# rpi_display_v2.net
KiCad netlist of a schematic drawn in EAGLE
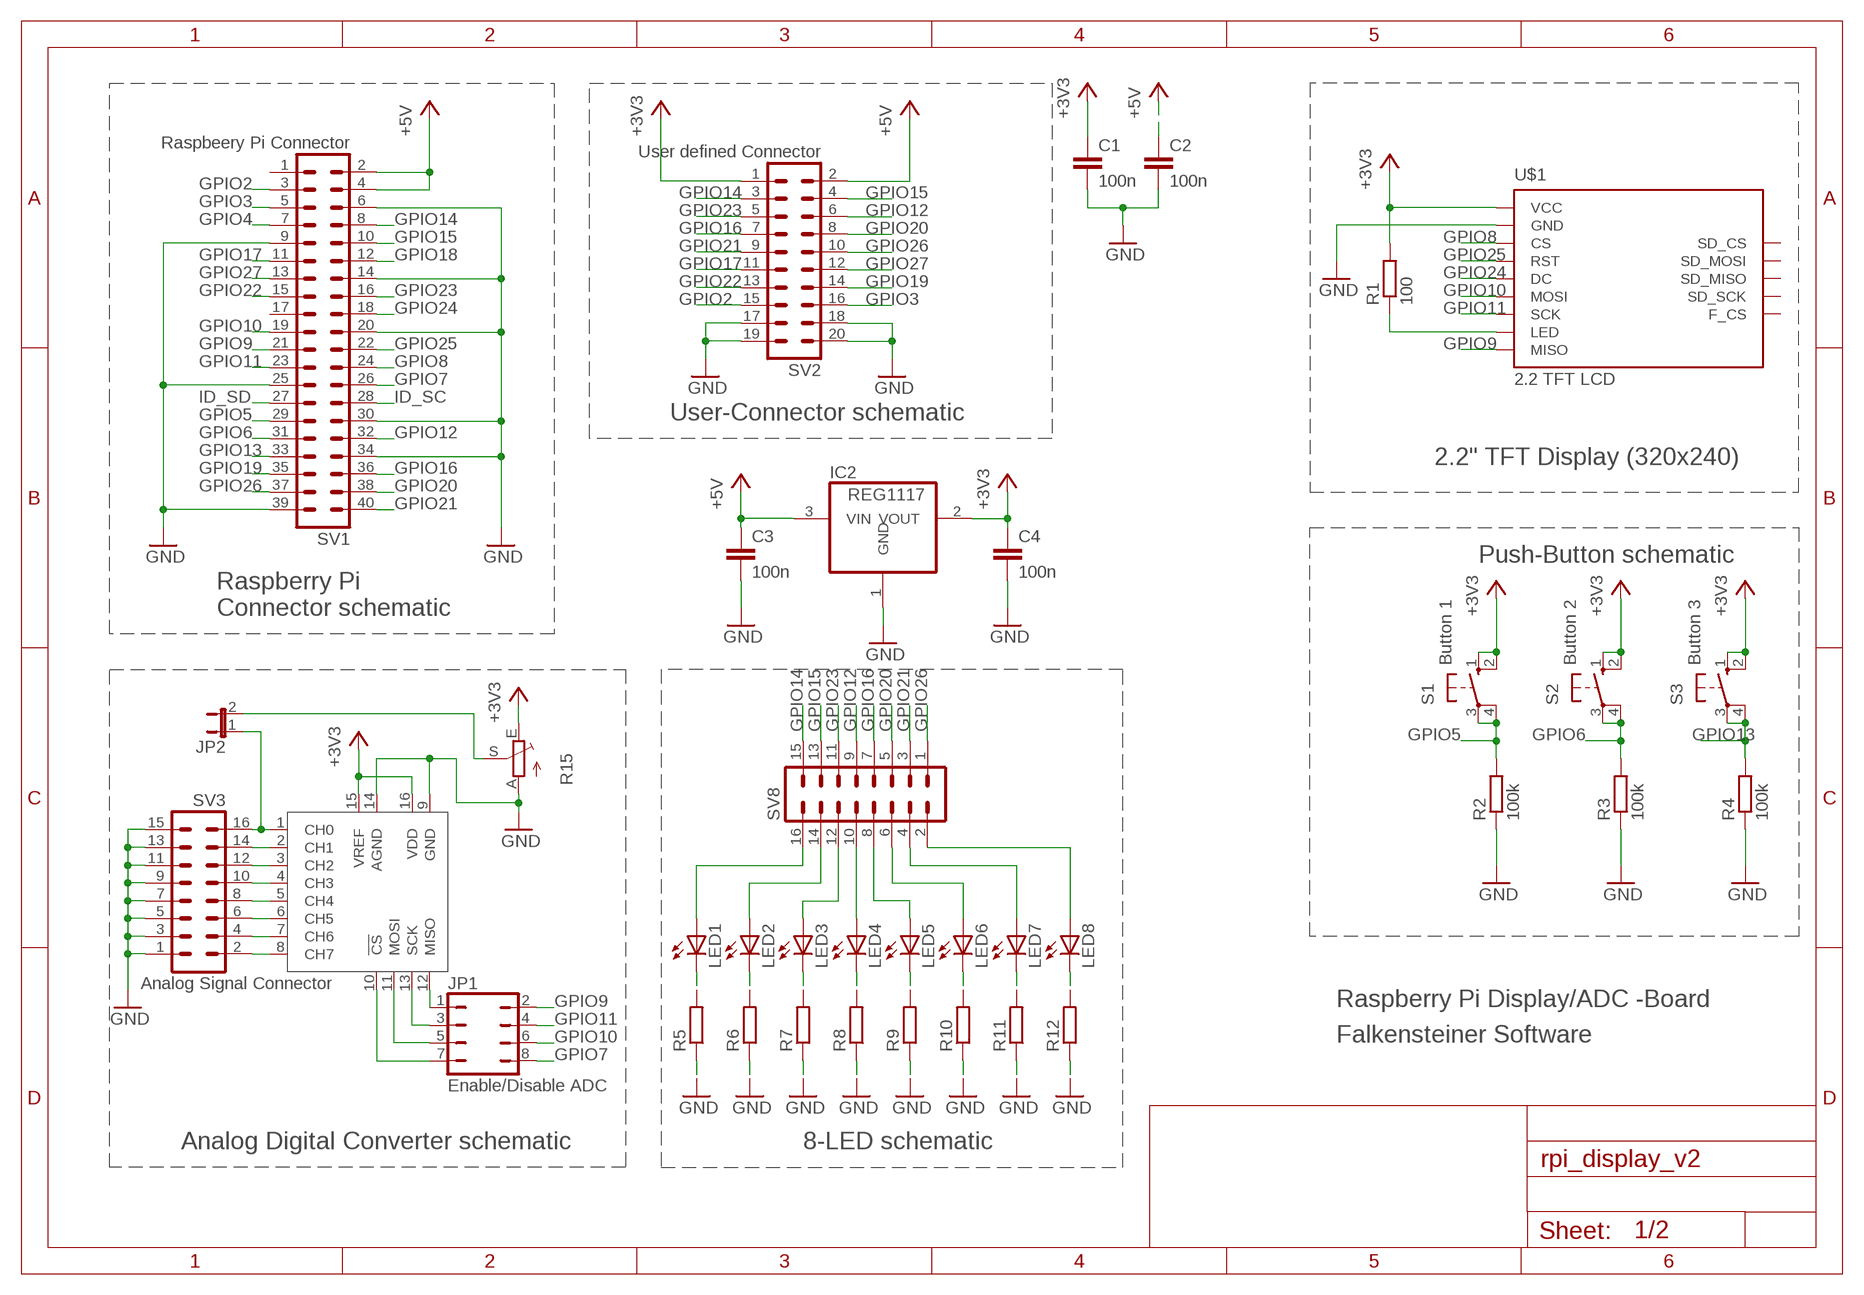
[diagram p0: schematic, sheet 1]
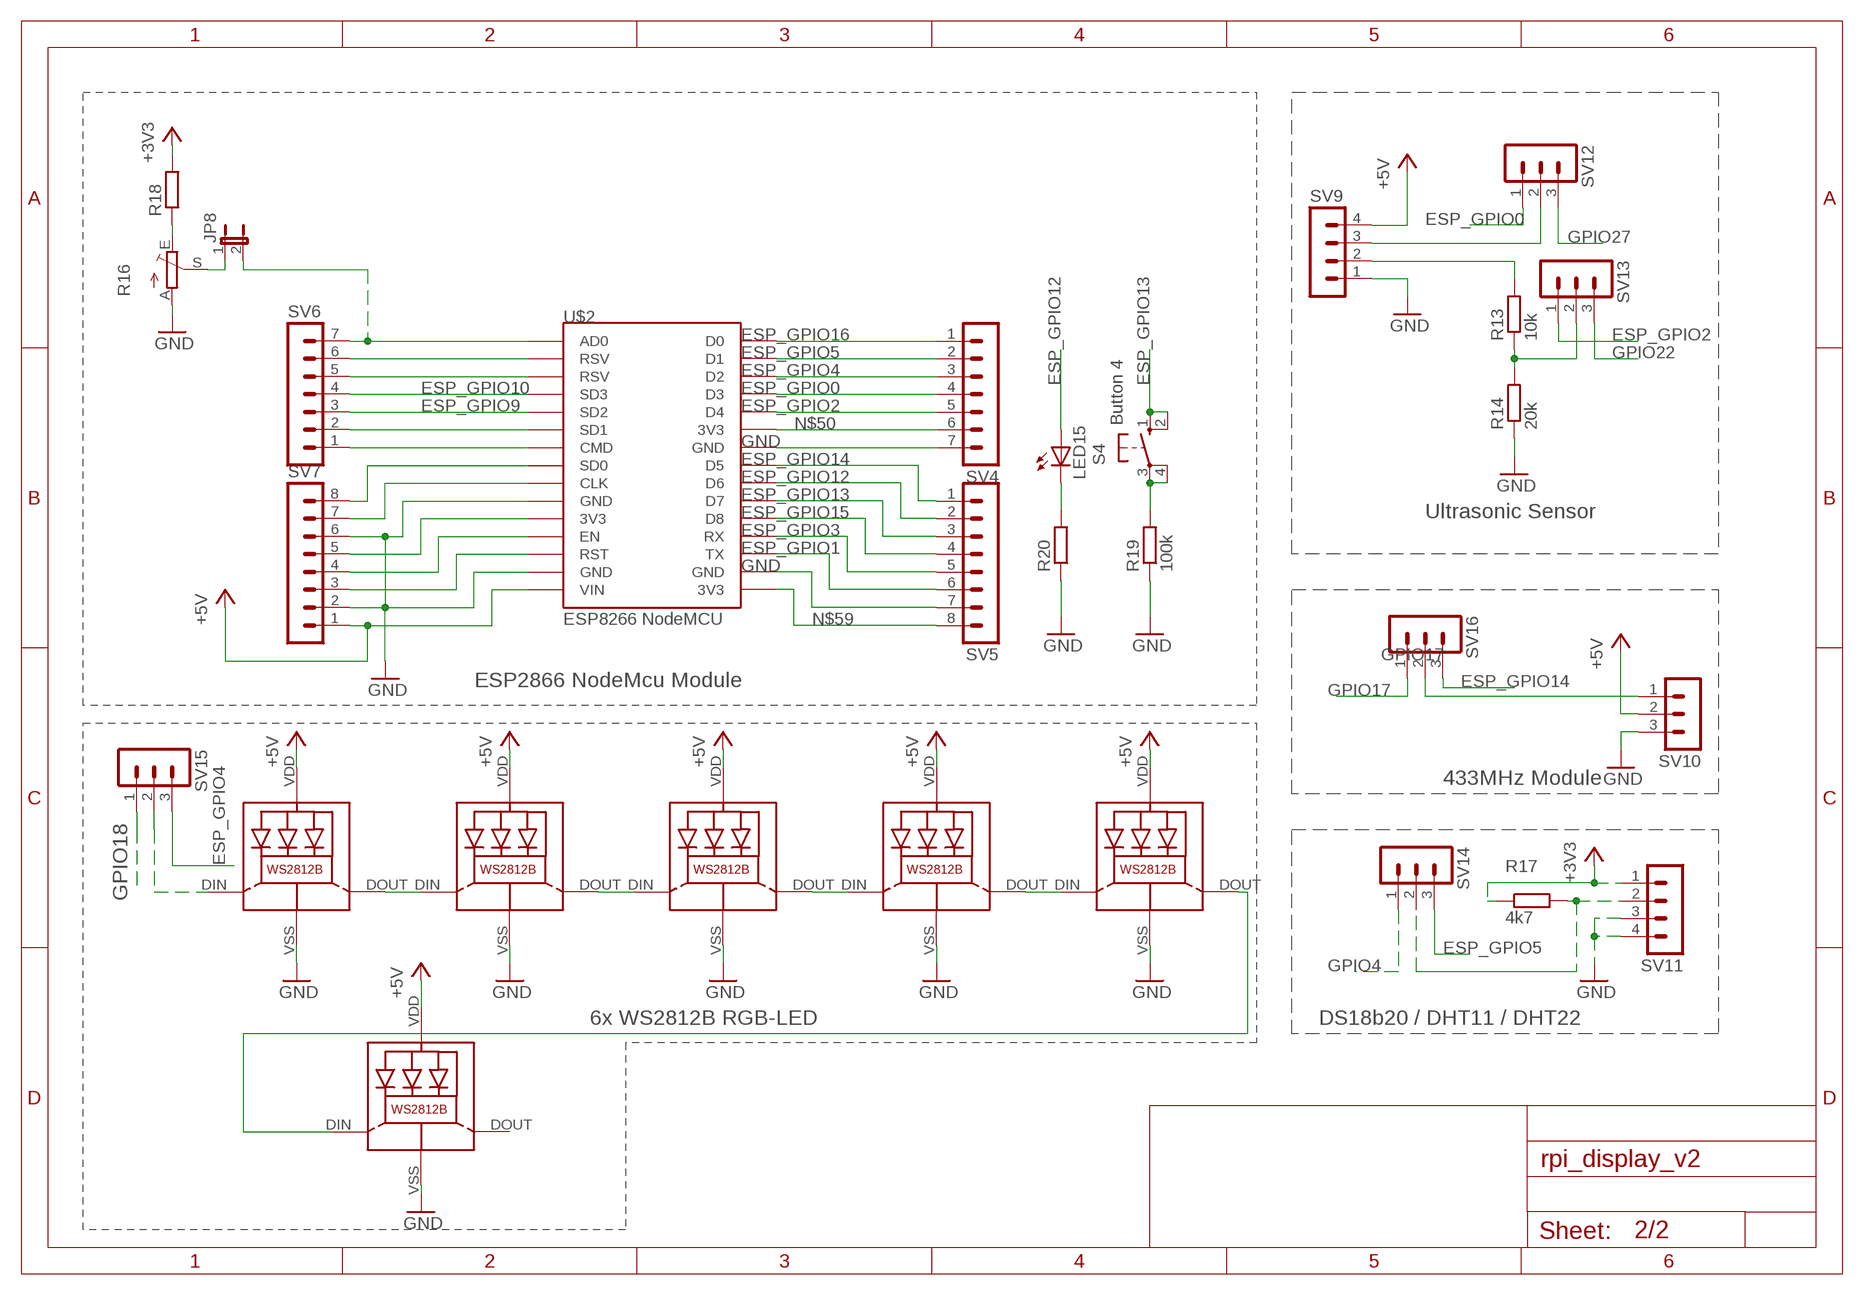
[diagram p1: schematic, sheet 2]

(export (version "E")
  (design (tool "Eeschema 10.0.6"))
  (components
    (comp (ref "JP8")
      (value "JP1E")
      (footprint "eagle-import:JP1")
      (libsource (lib "eagle-import") (part "JP1E"))
    )
    (comp (ref "LED9")
      (value "WS2812B")
      (footprint "eagle-import:WS2812B")
      (libsource (lib "eagle-import") (part "WS2812B"))
    )
    (comp (ref "LED10")
      (value "WS2812B")
      (footprint "eagle-import:WS2812B")
      (libsource (lib "eagle-import") (part "WS2812B"))
    )
    (comp (ref "LED11")
      (value "WS2812B")
      (footprint "eagle-import:WS2812B")
      (libsource (lib "eagle-import") (part "WS2812B"))
    )
    (comp (ref "LED12")
      (value "WS2812B")
      (footprint "eagle-import:WS2812B")
      (libsource (lib "eagle-import") (part "WS2812B"))
    )
    (comp (ref "LED13")
      (value "WS2812B")
      (footprint "eagle-import:WS2812B")
      (libsource (lib "eagle-import") (part "WS2812B"))
    )
    (comp (ref "LED14")
      (value "WS2812B")
      (footprint "eagle-import:WS2812B")
      (libsource (lib "eagle-import") (part "WS2812B"))
    )
    (comp (ref "LED15")
      (value "LEDSML1206")
      (footprint "eagle-import:SML1206")
      (libsource (lib "eagle-import") (part "LEDSML1206"))
    )
    (comp (ref "R13")
      (value "10k")
      (footprint "eagle-import:R1206")
      (libsource (lib "eagle-import") (part "R-EU_R1206"))
    )
    (comp (ref "R14")
      (value "20k")
      (footprint "eagle-import:R1206")
      (libsource (lib "eagle-import") (part "R-EU_R1206"))
    )
    (comp (ref "R16")
      (value "TRIM_EU-CA6V")
      (footprint "eagle-import:CA6V")
      (libsource (lib "eagle-import") (part "TRIM_EU-CA6V"))
    )
    (comp (ref "R17")
      (value "4k7")
      (footprint "eagle-import:R1206")
      (libsource (lib "eagle-import") (part "R-EU_R1206"))
    )
    (comp (ref "R18")
      (value "R-EU_R1206")
      (footprint "eagle-import:R1206")
      (libsource (lib "eagle-import") (part "R-EU_R1206"))
    )
    (comp (ref "R19")
      (value "100k")
      (footprint "eagle-import:R1206")
      (libsource (lib "eagle-import") (part "R-EU_R1206"))
    )
    (comp (ref "R20")
      (value "R-EU_R1206")
      (footprint "eagle-import:R1206")
      (libsource (lib "eagle-import") (part "R-EU_R1206"))
    )
    (comp (ref "S4")
      (value "Button 4")
      (footprint "eagle-import:B3F-10XX")
      (fields (field (name "MPN") "B3F-1000"))
      (libsource (lib "eagle-import") (part "10-XX"))
    )
    (comp (ref "SV4")
      (value "MA07-1")
      (footprint "eagle-import:MA07-1")
      (libsource (lib "eagle-import") (part "MA07-1"))
    )
    (comp (ref "SV5")
      (value "MA08-1")
      (footprint "eagle-import:MA08-1")
      (libsource (lib "eagle-import") (part "MA08-1"))
    )
    (comp (ref "SV6")
      (value "MA07-1")
      (footprint "eagle-import:MA07-1")
      (libsource (lib "eagle-import") (part "MA07-1"))
    )
    (comp (ref "SV7")
      (value "MA08-1")
      (footprint "eagle-import:MA08-1")
      (libsource (lib "eagle-import") (part "MA08-1"))
    )
    (comp (ref "SV9")
      (value "MA04-1")
      (footprint "eagle-import:MA04-1")
      (libsource (lib "eagle-import") (part "MA04-1"))
    )
    (comp (ref "SV10")
      (value "MA03-1")
      (footprint "eagle-import:MA03-1")
      (libsource (lib "eagle-import") (part "MA03-1"))
    )
    (comp (ref "SV11")
      (value "MA04-1")
      (footprint "eagle-import:MA04-1")
      (libsource (lib "eagle-import") (part "MA04-1"))
    )
    (comp (ref "SV12")
      (value "MA03-1")
      (footprint "eagle-import:MA03-1")
      (libsource (lib "eagle-import") (part "MA03-1"))
    )
    (comp (ref "SV13")
      (value "MA03-1")
      (footprint "eagle-import:MA03-1")
      (libsource (lib "eagle-import") (part "MA03-1"))
    )
    (comp (ref "SV14")
      (value "MA03-1")
      (footprint "eagle-import:MA03-1")
      (libsource (lib "eagle-import") (part "MA03-1"))
    )
    (comp (ref "SV15")
      (value "MA03-1")
      (footprint "eagle-import:MA03-1")
      (libsource (lib "eagle-import") (part "MA03-1"))
    )
    (comp (ref "SV16")
      (value "MA03-1")
      (footprint "eagle-import:MA03-1")
      (libsource (lib "eagle-import") (part "MA03-1"))
    )
    (comp (ref "U$2")
      (value "ESP8266 NodeMCU")
      (footprint "eagle-import:ESP12E_DEVKIT")
      (libsource (lib "eagle-import") (part "ESP12E_DEVKIT"))
    )
    (comp (ref "C1")
      (value "100n")
      (footprint "eagle-import:C1206")
      (libsource (lib "eagle-import") (part "C-EUC1206"))
    )
    (comp (ref "C2")
      (value "100n")
      (footprint "eagle-import:C1206")
      (libsource (lib "eagle-import") (part "C-EUC1206"))
    )
    (comp (ref "C3")
      (value "100n")
      (footprint "eagle-import:C1206")
      (libsource (lib "eagle-import") (part "C-EUC1206"))
    )
    (comp (ref "C4")
      (value "100n")
      (footprint "eagle-import:C1206")
      (libsource (lib "eagle-import") (part "C-EUC1206"))
    )
    (comp (ref "IC1")
      (value "MCP3008P")
      (footprint "eagle-import:DIL16")
      (libsource (lib "eagle-import") (part "MCP3008P"))
    )
    (comp (ref "IC2")
      (value "REG1117")
      (footprint "eagle-import:SOT223")
      (libsource (lib "eagle-import") (part "REG1117"))
    )
    (comp (ref "JP1")
      (value "Enable/Disable ADC")
      (footprint "eagle-import:JP4Q")
      (libsource (lib "eagle-import") (part "JP4Q"))
    )
    (comp (ref "JP2")
      (value "JP1E")
      (footprint "eagle-import:JP1")
      (libsource (lib "eagle-import") (part "JP1E"))
    )
    (comp (ref "LED1")
      (value "LEDSML1206")
      (footprint "eagle-import:SML1206")
      (libsource (lib "eagle-import") (part "LEDSML1206"))
    )
    (comp (ref "LED2")
      (value "LEDSML1206")
      (footprint "eagle-import:SML1206")
      (libsource (lib "eagle-import") (part "LEDSML1206"))
    )
    (comp (ref "LED3")
      (value "LEDSML1206")
      (footprint "eagle-import:SML1206")
      (libsource (lib "eagle-import") (part "LEDSML1206"))
    )
    (comp (ref "LED4")
      (value "LEDSML1206")
      (footprint "eagle-import:SML1206")
      (libsource (lib "eagle-import") (part "LEDSML1206"))
    )
    (comp (ref "LED5")
      (value "LEDSML1206")
      (footprint "eagle-import:SML1206")
      (libsource (lib "eagle-import") (part "LEDSML1206"))
    )
    (comp (ref "LED6")
      (value "LEDSML1206")
      (footprint "eagle-import:SML1206")
      (libsource (lib "eagle-import") (part "LEDSML1206"))
    )
    (comp (ref "LED7")
      (value "LEDSML1206")
      (footprint "eagle-import:SML1206")
      (libsource (lib "eagle-import") (part "LEDSML1206"))
    )
    (comp (ref "LED8")
      (value "LEDSML1206")
      (footprint "eagle-import:SML1206")
      (libsource (lib "eagle-import") (part "LEDSML1206"))
    )
    (comp (ref "R1")
      (value "100")
      (footprint "eagle-import:R1206")
      (libsource (lib "eagle-import") (part "R-EU_R1206"))
    )
    (comp (ref "R2")
      (value "100k")
      (footprint "eagle-import:R1206")
      (libsource (lib "eagle-import") (part "R-EU_R1206"))
    )
    (comp (ref "R3")
      (value "100k")
      (footprint "eagle-import:R1206")
      (libsource (lib "eagle-import") (part "R-EU_R1206"))
    )
    (comp (ref "R4")
      (value "100k")
      (footprint "eagle-import:R1206")
      (libsource (lib "eagle-import") (part "R-EU_R1206"))
    )
    (comp (ref "R5")
      (value "R-EU_R1206")
      (footprint "eagle-import:R1206")
      (libsource (lib "eagle-import") (part "R-EU_R1206"))
    )
    (comp (ref "R6")
      (value "R-EU_R1206")
      (footprint "eagle-import:R1206")
      (libsource (lib "eagle-import") (part "R-EU_R1206"))
    )
    (comp (ref "R7")
      (value "R-EU_R1206")
      (footprint "eagle-import:R1206")
      (libsource (lib "eagle-import") (part "R-EU_R1206"))
    )
    (comp (ref "R8")
      (value "R-EU_R1206")
      (footprint "eagle-import:R1206")
      (libsource (lib "eagle-import") (part "R-EU_R1206"))
    )
    (comp (ref "R9")
      (value "R-EU_R1206")
      (footprint "eagle-import:R1206")
      (libsource (lib "eagle-import") (part "R-EU_R1206"))
    )
    (comp (ref "R10")
      (value "R-EU_R1206")
      (footprint "eagle-import:R1206")
      (libsource (lib "eagle-import") (part "R-EU_R1206"))
    )
    (comp (ref "R11")
      (value "R-EU_R1206")
      (footprint "eagle-import:R1206")
      (libsource (lib "eagle-import") (part "R-EU_R1206"))
    )
    (comp (ref "R12")
      (value "R-EU_R1206")
      (footprint "eagle-import:R1206")
      (libsource (lib "eagle-import") (part "R-EU_R1206"))
    )
    (comp (ref "R15")
      (value "TRIM_EU-CA6V")
      (footprint "eagle-import:CA6V")
      (libsource (lib "eagle-import") (part "TRIM_EU-CA6V"))
    )
    (comp (ref "S1")
      (value "Button 1")
      (footprint "eagle-import:B3F-10XX")
      (fields (field (name "MPN") "B3F-1000"))
      (libsource (lib "eagle-import") (part "10-XX"))
    )
    (comp (ref "S2")
      (value "Button 2")
      (footprint "eagle-import:B3F-10XX")
      (fields (field (name "MPN") "B3F-1000"))
      (libsource (lib "eagle-import") (part "10-XX"))
    )
    (comp (ref "S3")
      (value "Button 3")
      (footprint "eagle-import:B3F-10XX")
      (fields (field (name "MPN") "B3F-1000"))
      (libsource (lib "eagle-import") (part "10-XX"))
    )
    (comp (ref "SV1")
      (value "Raspbeery Pi Connector")
      (footprint "eagle-import:MA20-2")
      (libsource (lib "eagle-import") (part "MA20-2"))
    )
    (comp (ref "SV2")
      (value "User defined Connector")
      (footprint "eagle-import:MA10-2")
      (libsource (lib "eagle-import") (part "MA10-2"))
    )
    (comp (ref "SV3")
      (value "Analog Signal Connector")
      (footprint "eagle-import:MA08-2")
      (libsource (lib "eagle-import") (part "MA08-2"))
    )
    (comp (ref "SV8")
      (value "MA08-2")
      (footprint "eagle-import:MA08-2")
      (libsource (lib "eagle-import") (part "MA08-2"))
    )
    (comp (ref "U$1")
      (value "2.2_TFT_LCD")
      (footprint "eagle-import:2.2_TFT_LCD")
      (libsource (lib "eagle-import") (part "2.2_TFT_LCD"))
    )
  )
  (nets
    (net (code "1") (name "+3V3") (class "Default")
      (node (ref "C1") (pin "1") (pinfunction "1_1") (pintype "passive"))
      (node (ref "C4") (pin "1") (pinfunction "1_1") (pintype "passive"))
      (node (ref "IC1") (pin "15") (pinfunction "VREF_15") (pintype "power_in"))
      (node (ref "IC1") (pin "16") (pinfunction "VDD_16") (pintype "power_in"))
      (node (ref "IC2") (pin "2") (pinfunction "VOUT_2") (pintype "output"))
      (node (ref "R1") (pin "2") (pinfunction "2_2") (pintype "passive"))
      (node (ref "R15") (pin "E") (pinfunction "E_E") (pintype "passive"))
      (node (ref "R17") (pin "1") (pinfunction "1_1") (pintype "passive"))
      (node (ref "R18") (pin "2") (pinfunction "2_2") (pintype "passive"))
      (node (ref "S1") (pin "1") (pinfunction "S_1") (pintype "passive"))
      (node (ref "S1") (pin "2") (pinfunction "S1_2") (pintype "passive"))
      (node (ref "S2") (pin "1") (pinfunction "S_1") (pintype "passive"))
      (node (ref "S2") (pin "2") (pinfunction "S1_2") (pintype "passive"))
      (node (ref "S3") (pin "1") (pinfunction "S_1") (pintype "passive"))
      (node (ref "S3") (pin "2") (pinfunction "S1_2") (pintype "passive"))
      (node (ref "SV11") (pin "1") (pinfunction "1_1") (pintype "passive"))
      (node (ref "SV2") (pin "1") (pinfunction "1_1") (pintype "passive"))
      (node (ref "U$1") (pin "VCC") (pinfunction "VCC_VCC") (pintype "power_in"))
    )
    (net (code "2") (name "+5V") (class "Default")
      (node (ref "C2") (pin "1") (pinfunction "1_1") (pintype "passive"))
      (node (ref "C3") (pin "1") (pinfunction "1_1") (pintype "passive"))
      (node (ref "IC2") (pin "3") (pinfunction "VIN_3") (pintype "input"))
      (node (ref "LED10") (pin "VDD") (pinfunction "VDD_VDD") (pintype "power_in"))
      (node (ref "LED11") (pin "VDD") (pinfunction "VDD_VDD") (pintype "power_in"))
      (node (ref "LED12") (pin "VDD") (pinfunction "VDD_VDD") (pintype "power_in"))
      (node (ref "LED13") (pin "VDD") (pinfunction "VDD_VDD") (pintype "power_in"))
      (node (ref "LED14") (pin "VDD") (pinfunction "VDD_VDD") (pintype "power_in"))
      (node (ref "LED9") (pin "VDD") (pinfunction "VDD_VDD") (pintype "power_in"))
      (node (ref "SV1") (pin "2") (pinfunction "2_2") (pintype "passive"))
      (node (ref "SV1") (pin "4") (pinfunction "4_4") (pintype "passive"))
      (node (ref "SV10") (pin "2") (pinfunction "2_2") (pintype "passive"))
      (node (ref "SV2") (pin "2") (pinfunction "2_2") (pintype "passive"))
      (node (ref "SV7") (pin "1") (pinfunction "1_1") (pintype "passive"))
      (node (ref "SV9") (pin "4") (pinfunction "4_4") (pintype "passive"))
      (node (ref "U$2") (pin "VIN") (pinfunction "VIN_VIN") (pintype "bidirectional"))
    )
    (net (code "3") (name "ESP_GPIO0") (class "Default")
      (node (ref "SV12") (pin "1") (pinfunction "1_1") (pintype "passive"))
      (node (ref "SV4") (pin "4") (pinfunction "4_4") (pintype "passive"))
      (node (ref "U$2") (pin "D3") (pinfunction "D3_D3") (pintype "bidirectional"))
    )
    (net (code "4") (name "ESP_GPIO1") (class "Default")
      (node (ref "SV5") (pin "6") (pinfunction "6_6") (pintype "passive"))
      (node (ref "U$2") (pin "TX") (pinfunction "TX_TX") (pintype "bidirectional"))
    )
    (net (code "5") (name "ESP_GPIO2") (class "Default")
      (node (ref "SV13") (pin "1") (pinfunction "1_1") (pintype "passive"))
      (node (ref "SV4") (pin "5") (pinfunction "5_5") (pintype "passive"))
      (node (ref "U$2") (pin "D4") (pinfunction "D4_D4") (pintype "bidirectional"))
    )
    (net (code "6") (name "ESP_GPIO3") (class "Default")
      (node (ref "SV5") (pin "5") (pinfunction "5_5") (pintype "passive"))
      (node (ref "U$2") (pin "RX") (pinfunction "RX_RX") (pintype "bidirectional"))
    )
    (net (code "7") (name "ESP_GPIO4") (class "Default")
      (node (ref "SV15") (pin "3") (pinfunction "3_3") (pintype "passive"))
      (node (ref "SV4") (pin "3") (pinfunction "3_3") (pintype "passive"))
      (node (ref "U$2") (pin "D2") (pinfunction "D2_D2") (pintype "bidirectional"))
    )
    (net (code "8") (name "ESP_GPIO5") (class "Default")
      (node (ref "SV14") (pin "3") (pinfunction "3_3") (pintype "passive"))
      (node (ref "SV4") (pin "2") (pinfunction "2_2") (pintype "passive"))
      (node (ref "U$2") (pin "D1") (pinfunction "D1_D1") (pintype "bidirectional"))
    )
    (net (code "9") (name "ESP_GPIO9") (class "Default")
      (node (ref "SV6") (pin "3") (pinfunction "3_3") (pintype "passive"))
      (node (ref "U$2") (pin "SD2") (pinfunction "SD2_SD2") (pintype "bidirectional"))
    )
    (net (code "10") (name "ESP_GPIO10") (class "Default")
      (node (ref "SV6") (pin "4") (pinfunction "4_4") (pintype "passive"))
      (node (ref "U$2") (pin "SD3") (pinfunction "SD3_SD3") (pintype "bidirectional"))
    )
    (net (code "11") (name "ESP_GPIO12") (class "Default")
      (node (ref "LED15") (pin "A") (pinfunction "A_A") (pintype "passive"))
      (node (ref "SV5") (pin "2") (pinfunction "2_2") (pintype "passive"))
      (node (ref "U$2") (pin "D6") (pinfunction "D6_D6") (pintype "bidirectional"))
    )
    (net (code "12") (name "ESP_GPIO13") (class "Default")
      (node (ref "S4") (pin "1") (pinfunction "S_1") (pintype "passive"))
      (node (ref "S4") (pin "2") (pinfunction "S1_2") (pintype "passive"))
      (node (ref "SV5") (pin "3") (pinfunction "3_3") (pintype "passive"))
      (node (ref "U$2") (pin "D7") (pinfunction "D7_D7") (pintype "bidirectional"))
    )
    (net (code "13") (name "ESP_GPIO14") (class "Default")
      (node (ref "SV16") (pin "3") (pinfunction "3_3") (pintype "passive"))
      (node (ref "SV5") (pin "1") (pinfunction "1_1") (pintype "passive"))
      (node (ref "U$2") (pin "D5") (pinfunction "D5_D5") (pintype "bidirectional"))
    )
    (net (code "14") (name "ESP_GPIO15") (class "Default")
      (node (ref "SV5") (pin "4") (pinfunction "4_4") (pintype "passive"))
      (node (ref "U$2") (pin "D8") (pinfunction "D8_D8") (pintype "bidirectional"))
    )
    (net (code "15") (name "ESP_GPIO16") (class "Default")
      (node (ref "SV4") (pin "1") (pinfunction "1_1") (pintype "passive"))
      (node (ref "U$2") (pin "D0") (pinfunction "D0_D0") (pintype "bidirectional"))
    )
    (net (code "16") (name "GND") (class "Default")
      (node (ref "C1") (pin "2") (pinfunction "2_2") (pintype "passive"))
      (node (ref "C2") (pin "2") (pinfunction "2_2") (pintype "passive"))
      (node (ref "C3") (pin "2") (pinfunction "2_2") (pintype "passive"))
      (node (ref "C4") (pin "2") (pinfunction "2_2") (pintype "passive"))
      (node (ref "IC1") (pin "14") (pinfunction "AGND_14") (pintype "power_in"))
      (node (ref "IC1") (pin "9") (pinfunction "GND_9") (pintype "power_in"))
      (node (ref "IC2") (pin "1") (pinfunction "GND_1") (pintype "power_in"))
      (node (ref "LED10") (pin "VSS") (pinfunction "GND_VSS") (pintype "power_in"))
      (node (ref "LED11") (pin "VSS") (pinfunction "GND_VSS") (pintype "power_in"))
      (node (ref "LED12") (pin "VSS") (pinfunction "GND_VSS") (pintype "power_in"))
      (node (ref "LED13") (pin "VSS") (pinfunction "GND_VSS") (pintype "power_in"))
      (node (ref "LED14") (pin "VSS") (pinfunction "GND_VSS") (pintype "power_in"))
      (node (ref "LED9") (pin "VSS") (pinfunction "GND_VSS") (pintype "power_in"))
      (node (ref "R10") (pin "1") (pinfunction "1_1") (pintype "passive"))
      (node (ref "R11") (pin "1") (pinfunction "1_1") (pintype "passive"))
      (node (ref "R12") (pin "1") (pinfunction "1_1") (pintype "passive"))
      (node (ref "R14") (pin "1") (pinfunction "1_1") (pintype "passive"))
      (node (ref "R15") (pin "A") (pinfunction "A_A") (pintype "passive"))
      (node (ref "R16") (pin "A") (pinfunction "A_A") (pintype "passive"))
      (node (ref "R19") (pin "1") (pinfunction "1_1") (pintype "passive"))
      (node (ref "R2") (pin "1") (pinfunction "1_1") (pintype "passive"))
      (node (ref "R20") (pin "1") (pinfunction "1_1") (pintype "passive"))
      (node (ref "R3") (pin "1") (pinfunction "1_1") (pintype "passive"))
      (node (ref "R4") (pin "1") (pinfunction "1_1") (pintype "passive"))
      (node (ref "R5") (pin "1") (pinfunction "1_1") (pintype "passive"))
      (node (ref "R6") (pin "1") (pinfunction "1_1") (pintype "passive"))
      (node (ref "R7") (pin "1") (pinfunction "1_1") (pintype "passive"))
      (node (ref "R8") (pin "1") (pinfunction "1_1") (pintype "passive"))
      (node (ref "R9") (pin "1") (pinfunction "1_1") (pintype "passive"))
      (node (ref "SV1") (pin "14") (pinfunction "14_14") (pintype "passive"))
      (node (ref "SV1") (pin "20") (pinfunction "20_20") (pintype "passive"))
      (node (ref "SV1") (pin "25") (pinfunction "25_25") (pintype "passive"))
      (node (ref "SV1") (pin "30") (pinfunction "30_30") (pintype "passive"))
      (node (ref "SV1") (pin "34") (pinfunction "34_34") (pintype "passive"))
      (node (ref "SV1") (pin "39") (pinfunction "39_39") (pintype "passive"))
      (node (ref "SV1") (pin "6") (pinfunction "6_6") (pintype "passive"))
      (node (ref "SV1") (pin "9") (pinfunction "9_9") (pintype "passive"))
      (node (ref "SV10") (pin "3") (pinfunction "3_3") (pintype "passive"))
      (node (ref "SV11") (pin "3") (pinfunction "3_3") (pintype "passive"))
      (node (ref "SV11") (pin "4") (pinfunction "4_4") (pintype "passive"))
      (node (ref "SV2") (pin "17") (pinfunction "17_17") (pintype "passive"))
      (node (ref "SV2") (pin "18") (pinfunction "18_18") (pintype "passive"))
      (node (ref "SV2") (pin "19") (pinfunction "19_19") (pintype "passive"))
      (node (ref "SV2") (pin "20") (pinfunction "20_20") (pintype "passive"))
      (node (ref "SV3") (pin "1") (pinfunction "1_1") (pintype "passive"))
      (node (ref "SV3") (pin "11") (pinfunction "11_11") (pintype "passive"))
      (node (ref "SV3") (pin "13") (pinfunction "13_13") (pintype "passive"))
      (node (ref "SV3") (pin "15") (pinfunction "15_15") (pintype "passive"))
      (node (ref "SV3") (pin "3") (pinfunction "3_3") (pintype "passive"))
      (node (ref "SV3") (pin "5") (pinfunction "5_5") (pintype "passive"))
      (node (ref "SV3") (pin "7") (pinfunction "7_7") (pintype "passive"))
      (node (ref "SV3") (pin "9") (pinfunction "9_9") (pintype "passive"))
      (node (ref "SV4") (pin "7") (pinfunction "7_7") (pintype "passive"))
      (node (ref "SV5") (pin "7") (pinfunction "7_7") (pintype "passive"))
      (node (ref "SV7") (pin "2") (pinfunction "2_2") (pintype "passive"))
      (node (ref "SV7") (pin "6") (pinfunction "6_6") (pintype "passive"))
      (node (ref "SV9") (pin "1") (pinfunction "1_1") (pintype "passive"))
      (node (ref "U$1") (pin "GND") (pinfunction "GND_GND") (pintype "power_in"))
      (node (ref "U$2") (pin "GND@0") (pinfunction "GND_GND@0") (pintype "bidirectional"))
      (node (ref "U$2") (pin "GND@1") (pinfunction "GND_GND@1") (pintype "bidirectional"))
      (node (ref "U$2") (pin "GND@2") (pinfunction "GND_GND@2") (pintype "bidirectional"))
      (node (ref "U$2") (pin "GND@3") (pinfunction "GND_GND@3") (pintype "bidirectional"))
    )
    (net (code "17") (name "GPIO2") (class "Default")
      (node (ref "SV1") (pin "3") (pinfunction "3_3") (pintype "passive"))
      (node (ref "SV2") (pin "15") (pinfunction "15_15") (pintype "passive"))
    )
    (net (code "18") (name "GPIO3") (class "Default")
      (node (ref "SV1") (pin "5") (pinfunction "5_5") (pintype "passive"))
      (node (ref "SV2") (pin "16") (pinfunction "16_16") (pintype "passive"))
    )
    (net (code "19") (name "GPIO4") (class "Default")
      (node (ref "SV1") (pin "7") (pinfunction "7_7") (pintype "passive"))
      (node (ref "SV14") (pin "1") (pinfunction "1_1") (pintype "passive"))
    )
    (net (code "20") (name "GPIO5") (class "Default")
      (node (ref "R2") (pin "2") (pinfunction "2_2") (pintype "passive"))
      (node (ref "S1") (pin "3") (pinfunction "P_3") (pintype "passive"))
      (node (ref "S1") (pin "4") (pinfunction "P1_4") (pintype "passive"))
      (node (ref "SV1") (pin "29") (pinfunction "29_29") (pintype "passive"))
    )
    (net (code "21") (name "GPIO6") (class "Default")
      (node (ref "R3") (pin "2") (pinfunction "2_2") (pintype "passive"))
      (node (ref "S2") (pin "3") (pinfunction "P_3") (pintype "passive"))
      (node (ref "S2") (pin "4") (pinfunction "P1_4") (pintype "passive"))
      (node (ref "SV1") (pin "31") (pinfunction "31_31") (pintype "passive"))
    )
    (net (code "22") (name "GPIO7") (class "Default")
      (node (ref "JP1") (pin "8") (pinfunction "8_8") (pintype "passive"))
      (node (ref "SV1") (pin "26") (pinfunction "26_26") (pintype "passive"))
    )
    (net (code "23") (name "GPIO8") (class "Default")
      (node (ref "SV1") (pin "24") (pinfunction "24_24") (pintype "passive"))
      (node (ref "U$1") (pin "CS") (pinfunction "CS_CS") (pintype "bidirectional"))
    )
    (net (code "24") (name "GPIO9") (class "Default")
      (node (ref "JP1") (pin "2") (pinfunction "2_2") (pintype "passive"))
      (node (ref "SV1") (pin "21") (pinfunction "21_21") (pintype "passive"))
      (node (ref "U$1") (pin "MISO") (pinfunction "MISO_MISO") (pintype "bidirectional"))
    )
    (net (code "25") (name "GPIO10") (class "Default")
      (node (ref "JP1") (pin "6") (pinfunction "6_6") (pintype "passive"))
      (node (ref "SV1") (pin "19") (pinfunction "19_19") (pintype "passive"))
      (node (ref "U$1") (pin "MOSI") (pinfunction "MOSI_MOSI") (pintype "bidirectional"))
    )
    (net (code "26") (name "GPIO11") (class "Default")
      (node (ref "JP1") (pin "4") (pinfunction "4_4") (pintype "passive"))
      (node (ref "SV1") (pin "23") (pinfunction "23_23") (pintype "passive"))
      (node (ref "U$1") (pin "SCK") (pinfunction "SCK_SCK") (pintype "bidirectional"))
    )
    (net (code "27") (name "GPIO12") (class "Default")
      (node (ref "SV1") (pin "32") (pinfunction "32_32") (pintype "passive"))
      (node (ref "SV2") (pin "6") (pinfunction "6_6") (pintype "passive"))
      (node (ref "SV8") (pin "9") (pinfunction "9_9") (pintype "passive"))
    )
    (net (code "28") (name "GPIO13") (class "Default")
      (node (ref "R4") (pin "2") (pinfunction "2_2") (pintype "passive"))
      (node (ref "S3") (pin "3") (pinfunction "P_3") (pintype "passive"))
      (node (ref "S3") (pin "4") (pinfunction "P1_4") (pintype "passive"))
      (node (ref "SV1") (pin "33") (pinfunction "33_33") (pintype "passive"))
    )
    (net (code "29") (name "GPIO14") (class "Default")
      (node (ref "SV1") (pin "8") (pinfunction "8_8") (pintype "passive"))
      (node (ref "SV2") (pin "3") (pinfunction "3_3") (pintype "passive"))
      (node (ref "SV8") (pin "15") (pinfunction "15_15") (pintype "passive"))
    )
    (net (code "30") (name "GPIO15") (class "Default")
      (node (ref "SV1") (pin "10") (pinfunction "10_10") (pintype "passive"))
      (node (ref "SV2") (pin "4") (pinfunction "4_4") (pintype "passive"))
      (node (ref "SV8") (pin "13") (pinfunction "13_13") (pintype "passive"))
    )
    (net (code "31") (name "GPIO16") (class "Default")
      (node (ref "SV1") (pin "36") (pinfunction "36_36") (pintype "passive"))
      (node (ref "SV2") (pin "7") (pinfunction "7_7") (pintype "passive"))
      (node (ref "SV8") (pin "7") (pinfunction "7_7") (pintype "passive"))
    )
    (net (code "32") (name "GPIO17") (class "Default")
      (node (ref "SV1") (pin "11") (pinfunction "11_11") (pintype "passive"))
      (node (ref "SV16") (pin "1") (pinfunction "1_1") (pintype "passive"))
      (node (ref "SV2") (pin "11") (pinfunction "11_11") (pintype "passive"))
    )
    (net (code "33") (name "GPIO18") (class "Default")
      (node (ref "SV1") (pin "12") (pinfunction "12_12") (pintype "passive"))
      (node (ref "SV15") (pin "1") (pinfunction "1_1") (pintype "passive"))
    )
    (net (code "34") (name "GPIO19") (class "Default")
      (node (ref "SV1") (pin "35") (pinfunction "35_35") (pintype "passive"))
      (node (ref "SV2") (pin "14") (pinfunction "14_14") (pintype "passive"))
    )
    (net (code "35") (name "GPIO20") (class "Default")
      (node (ref "SV1") (pin "38") (pinfunction "38_38") (pintype "passive"))
      (node (ref "SV2") (pin "8") (pinfunction "8_8") (pintype "passive"))
      (node (ref "SV8") (pin "5") (pinfunction "5_5") (pintype "passive"))
    )
    (net (code "36") (name "GPIO21") (class "Default")
      (node (ref "SV1") (pin "40") (pinfunction "40_40") (pintype "passive"))
      (node (ref "SV2") (pin "9") (pinfunction "9_9") (pintype "passive"))
      (node (ref "SV8") (pin "3") (pinfunction "3_3") (pintype "passive"))
    )
    (net (code "37") (name "GPIO22") (class "Default")
      (node (ref "SV1") (pin "15") (pinfunction "15_15") (pintype "passive"))
      (node (ref "SV13") (pin "3") (pinfunction "3_3") (pintype "passive"))
      (node (ref "SV2") (pin "13") (pinfunction "13_13") (pintype "passive"))
    )
    (net (code "38") (name "GPIO23") (class "Default")
      (node (ref "SV1") (pin "16") (pinfunction "16_16") (pintype "passive"))
      (node (ref "SV2") (pin "5") (pinfunction "5_5") (pintype "passive"))
      (node (ref "SV8") (pin "11") (pinfunction "11_11") (pintype "passive"))
    )
    (net (code "39") (name "GPIO24") (class "Default")
      (node (ref "SV1") (pin "18") (pinfunction "18_18") (pintype "passive"))
      (node (ref "U$1") (pin "DC") (pinfunction "DC_DC") (pintype "bidirectional"))
    )
    (net (code "40") (name "GPIO25") (class "Default")
      (node (ref "SV1") (pin "22") (pinfunction "22_22") (pintype "passive"))
      (node (ref "U$1") (pin "RST") (pinfunction "RST_RST") (pintype "bidirectional"))
    )
    (net (code "41") (name "GPIO26") (class "Default")
      (node (ref "SV1") (pin "37") (pinfunction "37_37") (pintype "passive"))
      (node (ref "SV2") (pin "10") (pinfunction "10_10") (pintype "passive"))
      (node (ref "SV8") (pin "1") (pinfunction "1_1") (pintype "passive"))
    )
    (net (code "42") (name "GPIO27") (class "Default")
      (node (ref "SV1") (pin "13") (pinfunction "13_13") (pintype "passive"))
      (node (ref "SV12") (pin "3") (pinfunction "3_3") (pintype "passive"))
      (node (ref "SV2") (pin "12") (pinfunction "12_12") (pintype "passive"))
    )
    (net (code "43") (name "ID_SC") (class "Default")
      (node (ref "SV1") (pin "28") (pinfunction "28_28") (pintype "passive"))
    )
    (net (code "44") (name "ID_SD") (class "Default")
      (node (ref "SV1") (pin "27") (pinfunction "27_27") (pintype "passive"))
    )
    (net (code "45") (name "N$50") (class "Default")
      (node (ref "SV4") (pin "6") (pinfunction "6_6") (pintype "passive"))
      (node (ref "U$2") (pin "3V3@1") (pinfunction "3V3_3V3@1") (pintype "bidirectional"))
    )
    (net (code "46") (name "N$59") (class "Default")
      (node (ref "SV5") (pin "8") (pinfunction "8_8") (pintype "passive"))
      (node (ref "U$2") (pin "3V3@2") (pinfunction "3V3_3V3@2") (pintype "bidirectional"))
    )
    (net (code "47") (name "Net-(IC1-CH0)") (class "Default")
      (node (ref "IC1") (pin "1") (pinfunction "CH0_1") (pintype "input"))
      (node (ref "JP2") (pin "1") (pinfunction "1_1") (pintype "passive"))
      (node (ref "SV3") (pin "16") (pinfunction "16_16") (pintype "passive"))
    )
    (net (code "48") (name "Net-(IC1-CH1)") (class "Default")
      (node (ref "IC1") (pin "2") (pinfunction "CH1_2") (pintype "input"))
      (node (ref "SV3") (pin "14") (pinfunction "14_14") (pintype "passive"))
    )
    (net (code "49") (name "Net-(IC1-CH2)") (class "Default")
      (node (ref "IC1") (pin "3") (pinfunction "CH2_3") (pintype "input"))
      (node (ref "SV3") (pin "12") (pinfunction "12_12") (pintype "passive"))
    )
    (net (code "50") (name "Net-(IC1-CH3)") (class "Default")
      (node (ref "IC1") (pin "4") (pinfunction "CH3_4") (pintype "input"))
      (node (ref "SV3") (pin "10") (pinfunction "10_10") (pintype "passive"))
    )
    (net (code "51") (name "Net-(IC1-CH4)") (class "Default")
      (node (ref "IC1") (pin "5") (pinfunction "CH4_5") (pintype "input"))
      (node (ref "SV3") (pin "8") (pinfunction "8_8") (pintype "passive"))
    )
    (net (code "52") (name "Net-(IC1-CH5)") (class "Default")
      (node (ref "IC1") (pin "6") (pinfunction "CH5_6") (pintype "input"))
      (node (ref "SV3") (pin "6") (pinfunction "6_6") (pintype "passive"))
    )
    (net (code "53") (name "Net-(IC1-CH6)") (class "Default")
      (node (ref "IC1") (pin "7") (pinfunction "CH6_7") (pintype "input"))
      (node (ref "SV3") (pin "4") (pinfunction "4_4") (pintype "passive"))
    )
    (net (code "54") (name "Net-(IC1-CH7)") (class "Default")
      (node (ref "IC1") (pin "8") (pinfunction "CH7_8") (pintype "input"))
      (node (ref "SV3") (pin "2") (pinfunction "2_2") (pintype "passive"))
    )
    (net (code "55") (name "Net-(IC1-MISO)") (class "Default")
      (node (ref "IC1") (pin "12") (pinfunction "MISO_12") (pintype "output"))
      (node (ref "JP1") (pin "1") (pinfunction "1_1") (pintype "passive"))
    )
    (net (code "56") (name "Net-(IC1-MOSI)") (class "Default")
      (node (ref "IC1") (pin "11") (pinfunction "MOSI_11") (pintype "input"))
      (node (ref "JP1") (pin "5") (pinfunction "5_5") (pintype "passive"))
    )
    (net (code "57") (name "Net-(IC1-SCK)") (class "Default")
      (node (ref "IC1") (pin "13") (pinfunction "SCK_13") (pintype "input"))
      (node (ref "JP1") (pin "3") (pinfunction "3_3") (pintype "passive"))
    )
    (net (code "58") (name "Net-(IC1-~{CS})") (class "Default")
      (node (ref "IC1") (pin "10") (pinfunction "~{CS}_10") (pintype "input"))
      (node (ref "JP1") (pin "7") (pinfunction "7_7") (pintype "passive"))
    )
    (net (code "59") (name "Net-(JP2-Pad2)") (class "Default")
      (node (ref "JP2") (pin "2") (pinfunction "2_2") (pintype "passive"))
      (node (ref "R15") (pin "S") (pinfunction "S_S") (pintype "passive"))
    )
    (net (code "60") (name "Net-(JP8-Pad1)") (class "Default")
      (node (ref "JP8") (pin "1") (pinfunction "1_1") (pintype "passive"))
      (node (ref "R16") (pin "S") (pinfunction "S_S") (pintype "passive"))
    )
    (net (code "61") (name "Net-(JP8-Pad2)") (class "Default")
      (node (ref "JP8") (pin "2") (pinfunction "2_2") (pintype "passive"))
      (node (ref "SV6") (pin "7") (pinfunction "7_7") (pintype "passive"))
      (node (ref "U$2") (pin "AD0") (pinfunction "AD0_AD0") (pintype "bidirectional"))
    )
    (net (code "62") (name "Net-(LED1-PadA)") (class "Default")
      (node (ref "LED1") (pin "A") (pinfunction "A_A") (pintype "passive"))
      (node (ref "SV8") (pin "16") (pinfunction "16_16") (pintype "passive"))
    )
    (net (code "63") (name "Net-(LED1-PadC)") (class "Default")
      (node (ref "LED1") (pin "C") (pinfunction "C_C") (pintype "passive"))
      (node (ref "R5") (pin "2") (pinfunction "2_2") (pintype "passive"))
    )
    (net (code "64") (name "Net-(LED2-PadA)") (class "Default")
      (node (ref "LED2") (pin "A") (pinfunction "A_A") (pintype "passive"))
      (node (ref "SV8") (pin "14") (pinfunction "14_14") (pintype "passive"))
    )
    (net (code "65") (name "Net-(LED2-PadC)") (class "Default")
      (node (ref "LED2") (pin "C") (pinfunction "C_C") (pintype "passive"))
      (node (ref "R6") (pin "2") (pinfunction "2_2") (pintype "passive"))
    )
    (net (code "66") (name "Net-(LED3-PadA)") (class "Default")
      (node (ref "LED3") (pin "A") (pinfunction "A_A") (pintype "passive"))
      (node (ref "SV8") (pin "12") (pinfunction "12_12") (pintype "passive"))
    )
    (net (code "67") (name "Net-(LED3-PadC)") (class "Default")
      (node (ref "LED3") (pin "C") (pinfunction "C_C") (pintype "passive"))
      (node (ref "R7") (pin "2") (pinfunction "2_2") (pintype "passive"))
    )
    (net (code "68") (name "Net-(LED4-PadA)") (class "Default")
      (node (ref "LED4") (pin "A") (pinfunction "A_A") (pintype "passive"))
      (node (ref "SV8") (pin "10") (pinfunction "10_10") (pintype "passive"))
    )
    (net (code "69") (name "Net-(LED4-PadC)") (class "Default")
      (node (ref "LED4") (pin "C") (pinfunction "C_C") (pintype "passive"))
      (node (ref "R8") (pin "2") (pinfunction "2_2") (pintype "passive"))
    )
    (net (code "70") (name "Net-(LED5-PadA)") (class "Default")
      (node (ref "LED5") (pin "A") (pinfunction "A_A") (pintype "passive"))
      (node (ref "SV8") (pin "8") (pinfunction "8_8") (pintype "passive"))
    )
    (net (code "71") (name "Net-(LED5-PadC)") (class "Default")
      (node (ref "LED5") (pin "C") (pinfunction "C_C") (pintype "passive"))
      (node (ref "R9") (pin "2") (pinfunction "2_2") (pintype "passive"))
    )
    (net (code "72") (name "Net-(LED6-PadA)") (class "Default")
      (node (ref "LED6") (pin "A") (pinfunction "A_A") (pintype "passive"))
      (node (ref "SV8") (pin "6") (pinfunction "6_6") (pintype "passive"))
    )
    (net (code "73") (name "Net-(LED6-PadC)") (class "Default")
      (node (ref "LED6") (pin "C") (pinfunction "C_C") (pintype "passive"))
      (node (ref "R10") (pin "2") (pinfunction "2_2") (pintype "passive"))
    )
    (net (code "74") (name "Net-(LED7-PadA)") (class "Default")
      (node (ref "LED7") (pin "A") (pinfunction "A_A") (pintype "passive"))
      (node (ref "SV8") (pin "4") (pinfunction "4_4") (pintype "passive"))
    )
    (net (code "75") (name "Net-(LED7-PadC)") (class "Default")
      (node (ref "LED7") (pin "C") (pinfunction "C_C") (pintype "passive"))
      (node (ref "R11") (pin "2") (pinfunction "2_2") (pintype "passive"))
    )
    (net (code "76") (name "Net-(LED8-PadA)") (class "Default")
      (node (ref "LED8") (pin "A") (pinfunction "A_A") (pintype "passive"))
      (node (ref "SV8") (pin "2") (pinfunction "2_2") (pintype "passive"))
    )
    (net (code "77") (name "Net-(LED8-PadC)") (class "Default")
      (node (ref "LED8") (pin "C") (pinfunction "C_C") (pintype "passive"))
      (node (ref "R12") (pin "2") (pinfunction "2_2") (pintype "passive"))
    )
    (net (code "78") (name "Net-(LED9-DI)") (class "Default")
      (node (ref "LED9") (pin "DIN") (pinfunction "DI_DIN") (pintype "input"))
      (node (ref "SV15") (pin "2") (pinfunction "2_2") (pintype "passive"))
    )
    (net (code "79") (name "Net-(LED10-DI)") (class "Default")
      (node (ref "LED10") (pin "DIN") (pinfunction "DI_DIN") (pintype "input"))
      (node (ref "LED9") (pin "DOUT") (pinfunction "DO_DOUT") (pintype "output"))
    )
    (net (code "80") (name "Net-(LED10-DO)") (class "Default")
      (node (ref "LED10") (pin "DOUT") (pinfunction "DO_DOUT") (pintype "output"))
      (node (ref "LED11") (pin "DIN") (pinfunction "DI_DIN") (pintype "input"))
    )
    (net (code "81") (name "Net-(LED11-DO)") (class "Default")
      (node (ref "LED11") (pin "DOUT") (pinfunction "DO_DOUT") (pintype "output"))
      (node (ref "LED12") (pin "DIN") (pinfunction "DI_DIN") (pintype "input"))
    )
    (net (code "82") (name "Net-(LED12-DO)") (class "Default")
      (node (ref "LED12") (pin "DOUT") (pinfunction "DO_DOUT") (pintype "output"))
      (node (ref "LED13") (pin "DIN") (pinfunction "DI_DIN") (pintype "input"))
    )
    (net (code "83") (name "Net-(LED13-DO)") (class "Default")
      (node (ref "LED13") (pin "DOUT") (pinfunction "DO_DOUT") (pintype "output"))
      (node (ref "LED14") (pin "DIN") (pinfunction "DI_DIN") (pintype "input"))
    )
    (net (code "84") (name "Net-(LED15-PadC)") (class "Default")
      (node (ref "LED15") (pin "C") (pinfunction "C_C") (pintype "passive"))
      (node (ref "R20") (pin "2") (pinfunction "2_2") (pintype "passive"))
    )
    (net (code "85") (name "Net-(R1-Pad1)") (class "Default")
      (node (ref "R1") (pin "1") (pinfunction "1_1") (pintype "passive"))
      (node (ref "U$1") (pin "LED") (pinfunction "LED_LED") (pintype "bidirectional"))
    )
    (net (code "86") (name "Net-(R13-Pad1)") (class "Default")
      (node (ref "R13") (pin "1") (pinfunction "1_1") (pintype "passive"))
      (node (ref "R14") (pin "2") (pinfunction "2_2") (pintype "passive"))
      (node (ref "SV13") (pin "2") (pinfunction "2_2") (pintype "passive"))
    )
    (net (code "87") (name "Net-(R13-Pad2)") (class "Default")
      (node (ref "R13") (pin "2") (pinfunction "2_2") (pintype "passive"))
      (node (ref "SV9") (pin "2") (pinfunction "2_2") (pintype "passive"))
    )
    (net (code "88") (name "Net-(R16-PadE)") (class "Default")
      (node (ref "R16") (pin "E") (pinfunction "E_E") (pintype "passive"))
      (node (ref "R18") (pin "1") (pinfunction "1_1") (pintype "passive"))
    )
    (net (code "89") (name "Net-(R17-Pad2)") (class "Default")
      (node (ref "R17") (pin "2") (pinfunction "2_2") (pintype "passive"))
      (node (ref "SV11") (pin "2") (pinfunction "2_2") (pintype "passive"))
      (node (ref "SV14") (pin "2") (pinfunction "2_2") (pintype "passive"))
    )
    (net (code "90") (name "Net-(S4-P)") (class "Default")
      (node (ref "R19") (pin "2") (pinfunction "2_2") (pintype "passive"))
      (node (ref "S4") (pin "3") (pinfunction "P_3") (pintype "passive"))
      (node (ref "S4") (pin "4") (pinfunction "P1_4") (pintype "passive"))
    )
    (net (code "91") (name "Net-(SV6-Pad1)") (class "Default")
      (node (ref "SV6") (pin "1") (pinfunction "1_1") (pintype "passive"))
      (node (ref "U$2") (pin "CMD") (pinfunction "CMD_CMD") (pintype "bidirectional"))
    )
    (net (code "92") (name "Net-(SV6-Pad2)") (class "Default")
      (node (ref "SV6") (pin "2") (pinfunction "2_2") (pintype "passive"))
      (node (ref "U$2") (pin "SD1") (pinfunction "SD1_SD1") (pintype "bidirectional"))
    )
    (net (code "93") (name "Net-(SV6-Pad5)") (class "Default")
      (node (ref "SV6") (pin "5") (pinfunction "5_5") (pintype "passive"))
      (node (ref "U$2") (pin "RSV@1") (pinfunction "RSV_RSV@1") (pintype "bidirectional"))
    )
    (net (code "94") (name "Net-(SV6-Pad6)") (class "Default")
      (node (ref "SV6") (pin "6") (pinfunction "6_6") (pintype "passive"))
      (node (ref "U$2") (pin "RSV@0") (pinfunction "RSV_RSV@0") (pintype "bidirectional"))
    )
    (net (code "95") (name "Net-(SV7-Pad3)") (class "Default")
      (node (ref "SV7") (pin "3") (pinfunction "3_3") (pintype "passive"))
      (node (ref "U$2") (pin "RST") (pinfunction "RST_RST") (pintype "bidirectional"))
    )
    (net (code "96") (name "Net-(SV7-Pad4)") (class "Default")
      (node (ref "SV7") (pin "4") (pinfunction "4_4") (pintype "passive"))
      (node (ref "U$2") (pin "EN") (pinfunction "EN_EN") (pintype "bidirectional"))
    )
    (net (code "97") (name "Net-(SV7-Pad5)") (class "Default")
      (node (ref "SV7") (pin "5") (pinfunction "5_5") (pintype "passive"))
      (node (ref "U$2") (pin "3V3@0") (pinfunction "3V3_3V3@0") (pintype "bidirectional"))
    )
    (net (code "98") (name "Net-(SV7-Pad7)") (class "Default")
      (node (ref "SV7") (pin "7") (pinfunction "7_7") (pintype "passive"))
      (node (ref "U$2") (pin "CLK") (pinfunction "CLK_CLK") (pintype "bidirectional"))
    )
    (net (code "99") (name "Net-(SV7-Pad8)") (class "Default")
      (node (ref "SV7") (pin "8") (pinfunction "8_8") (pintype "passive"))
      (node (ref "U$2") (pin "SD0") (pinfunction "SD0_SD0") (pintype "bidirectional"))
    )
    (net (code "100") (name "Net-(SV10-Pad1)") (class "Default")
      (node (ref "SV10") (pin "1") (pinfunction "1_1") (pintype "passive"))
      (node (ref "SV16") (pin "2") (pinfunction "2_2") (pintype "passive"))
    )
    (net (code "101") (name "Net-(SV12-Pad2)") (class "Default")
      (node (ref "SV12") (pin "2") (pinfunction "2_2") (pintype "passive"))
      (node (ref "SV9") (pin "3") (pinfunction "3_3") (pintype "passive"))
    )
    (net (code "102") (name "unconnected-(LED14-DO-PadDOUT)") (class "Default")
      (node (ref "LED14") (pin "DOUT") (pinfunction "DO_DOUT") (pintype "output"))
    )
    (net (code "103") (name "unconnected-(SV1-Pad1)") (class "Default")
      (node (ref "SV1") (pin "1") (pinfunction "1_1") (pintype "passive"))
    )
    (net (code "104") (name "unconnected-(SV1-Pad17)") (class "Default")
      (node (ref "SV1") (pin "17") (pinfunction "17_17") (pintype "passive"))
    )
    (net (code "105") (name "unconnected-(U$1-PadF_CS)") (class "Default")
      (node (ref "U$1") (pin "F_CS") (pinfunction "F_CS_F_CS") (pintype "bidirectional"))
    )
    (net (code "106") (name "unconnected-(U$1-PadSD_CS)") (class "Default")
      (node (ref "U$1") (pin "SD_CS") (pinfunction "SD_CS_SD_CS") (pintype "bidirectional"))
    )
    (net (code "107") (name "unconnected-(U$1-PadSD_MISO)") (class "Default")
      (node (ref "U$1") (pin "SD_MISO") (pinfunction "SD_MISO_SD_MISO") (pintype "bidirectional"))
    )
    (net (code "108") (name "unconnected-(U$1-PadSD_MOSI)") (class "Default")
      (node (ref "U$1") (pin "SD_MOSI") (pinfunction "SD_MOSI_SD_MOSI") (pintype "bidirectional"))
    )
    (net (code "109") (name "unconnected-(U$1-PadSD_SCK)") (class "Default")
      (node (ref "U$1") (pin "SD_SCK") (pinfunction "SD_SCK_SD_SCK") (pintype "bidirectional"))
    )
  )
)
